# negativeSupply_A.net
KiCad netlist of a schematic drawn in EAGLE
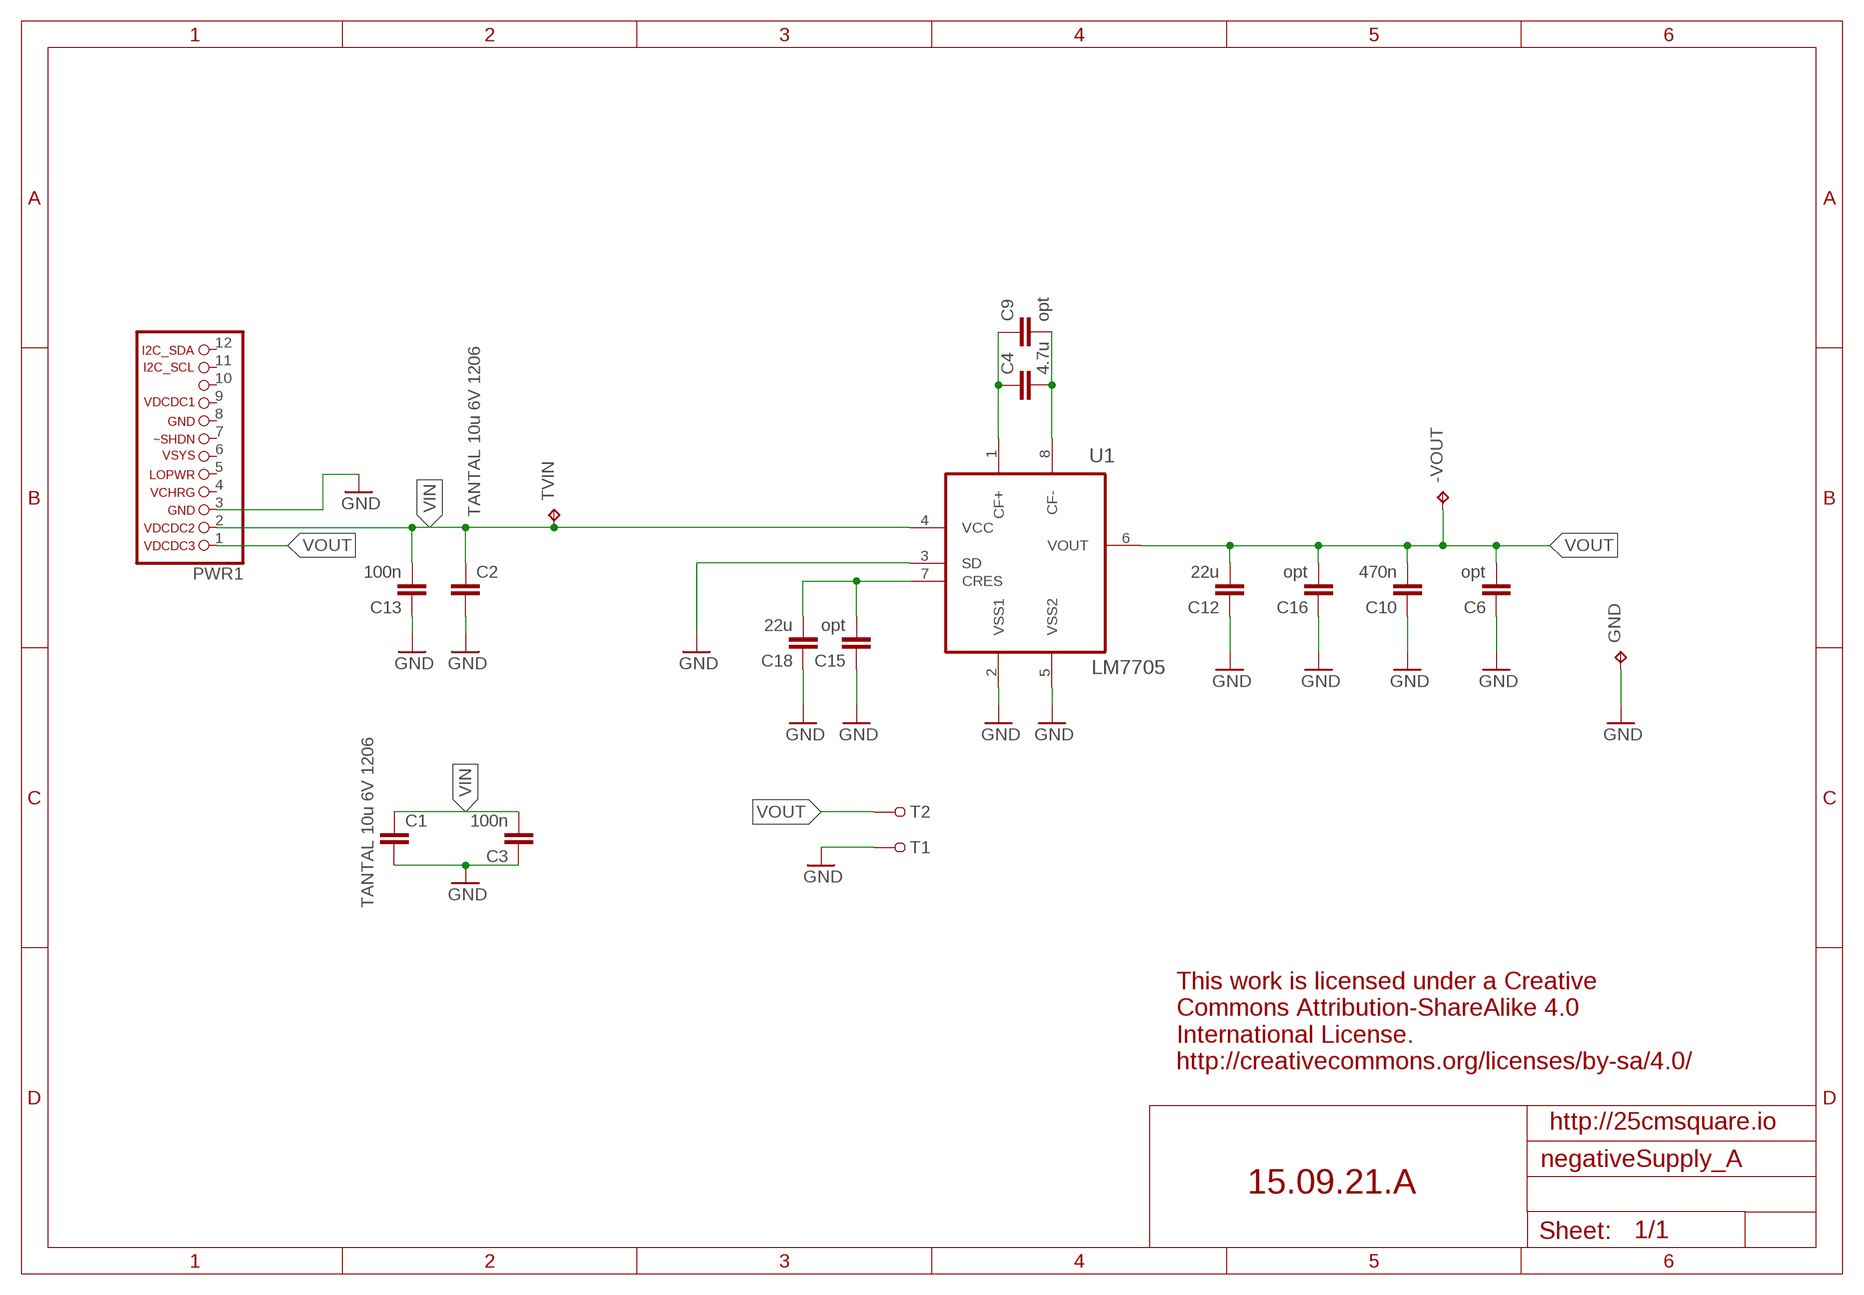
[diagram p0: schematic, sheet 1]

(export (version "E")
  (design (tool "Eeschema 10.0.6"))
  (components
    (comp (ref "-VOUT")
      (value "TPTP14R")
      (footprint "eagle-import:TP14R")
      (libsource (lib "eagle-import") (part "TPTP14R"))
    )
    (comp (ref "C1")
      (value "TANTAL 10u 6V 1206")
      (footprint "eagle-import:C1206K")
      (libsource (lib "eagle-import") (part "C-EUC1206K"))
    )
    (comp (ref "C2")
      (value "TANTAL 10u 6V 1206")
      (footprint "eagle-import:C1206K")
      (libsource (lib "eagle-import") (part "C-EUC1206K"))
    )
    (comp (ref "C3")
      (value "100n")
      (footprint "eagle-import:C0805K")
      (libsource (lib "eagle-import") (part "C-EUC0805K"))
    )
    (comp (ref "C4")
      (value "4.7u")
      (footprint "eagle-import:C0805K")
      (libsource (lib "eagle-import") (part "C-EUC0805K"))
    )
    (comp (ref "C6")
      (value "opt")
      (footprint "eagle-import:C0805K")
      (libsource (lib "eagle-import") (part "C-EUC0805K"))
    )
    (comp (ref "C9")
      (value "opt")
      (footprint "eagle-import:C0805K")
      (libsource (lib "eagle-import") (part "C-EUC0805K"))
    )
    (comp (ref "C10")
      (value "470n")
      (footprint "eagle-import:C0805K")
      (libsource (lib "eagle-import") (part "C-EUC0805K"))
    )
    (comp (ref "C12")
      (value "22u")
      (footprint "eagle-import:C0805K")
      (libsource (lib "eagle-import") (part "C-EUC0805K"))
    )
    (comp (ref "C13")
      (value "100n")
      (footprint "eagle-import:C0805K")
      (libsource (lib "eagle-import") (part "C-EUC0805K"))
    )
    (comp (ref "C15")
      (value "opt")
      (footprint "eagle-import:C0805K")
      (libsource (lib "eagle-import") (part "C-EUC0805K"))
    )
    (comp (ref "C16")
      (value "opt")
      (footprint "eagle-import:C0805K")
      (libsource (lib "eagle-import") (part "C-EUC0805K"))
    )
    (comp (ref "C18")
      (value "22u")
      (footprint "eagle-import:C0805K")
      (libsource (lib "eagle-import") (part "C-EUC0805K"))
    )
    (comp (ref "GND")
      (value "TPTP14R")
      (footprint "eagle-import:TP14R")
      (libsource (lib "eagle-import") (part "TPTP14R"))
    )
    (comp (ref "PWR1")
      (value "LIWE_12_PIN_PWR")
      (footprint "eagle-import:LIWE_12_PIN")
      (libsource (lib "eagle-import") (part "LIWE_12_PIN_PWR"))
    )
    (comp (ref "T1")
      (value "TEST-22-MULTICOMP")
      (footprint "eagle-import:TEST_1MM")
      (libsource (lib "eagle-import") (part "TEST-22-MULTICOMP"))
    )
    (comp (ref "T2")
      (value "TEST-22-MULTICOMP")
      (footprint "eagle-import:TEST_1MM")
      (libsource (lib "eagle-import") (part "TEST-22-MULTICOMP"))
    )
    (comp (ref "TVIN")
      (value "TPTP14R")
      (footprint "eagle-import:TP14R")
      (libsource (lib "eagle-import") (part "TPTP14R"))
    )
    (comp (ref "U1")
      (value "LM7705")
      (footprint "eagle-import:VSSOP-8")
      (libsource (lib "eagle-import") (part "LM7705"))
    )
  )
  (nets
    (net (code "1") (name "GND") (class "Default")
      (node (ref "C1") (pin "2") (pinfunction "2_2") (pintype "passive"))
      (node (ref "C10") (pin "1") (pinfunction "1_1") (pintype "passive"))
      (node (ref "C12") (pin "1") (pinfunction "1_1") (pintype "passive"))
      (node (ref "C13") (pin "1") (pinfunction "1_1") (pintype "passive"))
      (node (ref "C15") (pin "1") (pinfunction "1_1") (pintype "passive"))
      (node (ref "C16") (pin "1") (pinfunction "1_1") (pintype "passive"))
      (node (ref "C18") (pin "1") (pinfunction "1_1") (pintype "passive"))
      (node (ref "C2") (pin "2") (pinfunction "2_2") (pintype "passive"))
      (node (ref "C3") (pin "1") (pinfunction "1_1") (pintype "passive"))
      (node (ref "C6") (pin "1") (pinfunction "1_1") (pintype "passive"))
      (node (ref "GND") (pin "TP") (pinfunction "TP_TP") (pintype "input"))
      (node (ref "PWR1") (pin "3") (pinfunction "3_3") (pintype "passive"))
      (node (ref "T1") (pin "1") (pinfunction "1_1") (pintype "passive"))
      (node (ref "U1") (pin "2") (pinfunction "VSS1_2") (pintype "power_in"))
      (node (ref "U1") (pin "3") (pinfunction "SD_3") (pintype "input"))
      (node (ref "U1") (pin "5") (pinfunction "VSS2_5") (pintype "power_in"))
    )
    (net (code "2") (name "Net-(U1-CF+)") (class "Default")
      (node (ref "C4") (pin "1") (pinfunction "1_1") (pintype "passive"))
      (node (ref "C9") (pin "1") (pinfunction "1_1") (pintype "passive"))
      (node (ref "U1") (pin "1") (pinfunction "CF+_1") (pintype "passive"))
    )
    (net (code "3") (name "Net-(U1-CF-)") (class "Default")
      (node (ref "C4") (pin "2") (pinfunction "2_2") (pintype "passive"))
      (node (ref "C9") (pin "2") (pinfunction "2_2") (pintype "passive"))
      (node (ref "U1") (pin "8") (pinfunction "CF-_8") (pintype "passive"))
    )
    (net (code "4") (name "Net-(U1-CRES)") (class "Default")
      (node (ref "C15") (pin "2") (pinfunction "2_2") (pintype "passive"))
      (node (ref "C18") (pin "2") (pinfunction "2_2") (pintype "passive"))
      (node (ref "U1") (pin "7") (pinfunction "CRES_7") (pintype "passive"))
    )
    (net (code "5") (name "VIN") (class "Default")
      (node (ref "C1") (pin "1") (pinfunction "1_1") (pintype "passive"))
      (node (ref "C13") (pin "2") (pinfunction "2_2") (pintype "passive"))
      (node (ref "C2") (pin "1") (pinfunction "1_1") (pintype "passive"))
      (node (ref "C3") (pin "2") (pinfunction "2_2") (pintype "passive"))
      (node (ref "PWR1") (pin "2") (pinfunction "2_2") (pintype "passive"))
      (node (ref "TVIN") (pin "TP") (pinfunction "TP_TP") (pintype "input"))
      (node (ref "U1") (pin "4") (pinfunction "VCC_4") (pintype "power_in"))
    )
    (net (code "6") (name "VOUT") (class "Default")
      (node (ref "-VOUT") (pin "TP") (pinfunction "TP_TP") (pintype "input"))
      (node (ref "C10") (pin "2") (pinfunction "2_2") (pintype "passive"))
      (node (ref "C12") (pin "2") (pinfunction "2_2") (pintype "passive"))
      (node (ref "C16") (pin "2") (pinfunction "2_2") (pintype "passive"))
      (node (ref "C6") (pin "2") (pinfunction "2_2") (pintype "passive"))
      (node (ref "PWR1") (pin "1") (pinfunction "1_1") (pintype "passive"))
      (node (ref "T2") (pin "1") (pinfunction "1_1") (pintype "passive"))
      (node (ref "U1") (pin "6") (pinfunction "VOUT_6") (pintype "output"))
    )
    (net (code "7") (name "unconnected-(PWR1-Pad4)") (class "Default")
      (node (ref "PWR1") (pin "4") (pinfunction "4_4") (pintype "passive"))
    )
    (net (code "8") (name "unconnected-(PWR1-Pad5)") (class "Default")
      (node (ref "PWR1") (pin "5") (pinfunction "5_5") (pintype "passive"))
    )
    (net (code "9") (name "unconnected-(PWR1-Pad6)") (class "Default")
      (node (ref "PWR1") (pin "6") (pinfunction "6_6") (pintype "passive"))
    )
    (net (code "10") (name "unconnected-(PWR1-Pad7)") (class "Default")
      (node (ref "PWR1") (pin "7") (pinfunction "7_7") (pintype "passive"))
    )
    (net (code "11") (name "unconnected-(PWR1-Pad8)") (class "Default")
      (node (ref "PWR1") (pin "8") (pinfunction "8_8") (pintype "passive"))
    )
    (net (code "12") (name "unconnected-(PWR1-Pad9)") (class "Default")
      (node (ref "PWR1") (pin "9") (pinfunction "9_9") (pintype "passive"))
    )
    (net (code "13") (name "unconnected-(PWR1-Pad10)") (class "Default")
      (node (ref "PWR1") (pin "10") (pinfunction "10_10") (pintype "passive"))
    )
    (net (code "14") (name "unconnected-(PWR1-Pad11)") (class "Default")
      (node (ref "PWR1") (pin "11") (pinfunction "11_11") (pintype "passive"))
    )
    (net (code "15") (name "unconnected-(PWR1-Pad12)") (class "Default")
      (node (ref "PWR1") (pin "12") (pinfunction "12_12") (pintype "passive"))
    )
  )
)
